# STeaMi-FP5-Microphone.net
KiCad netlist of a schematic drawn in Altium Designer
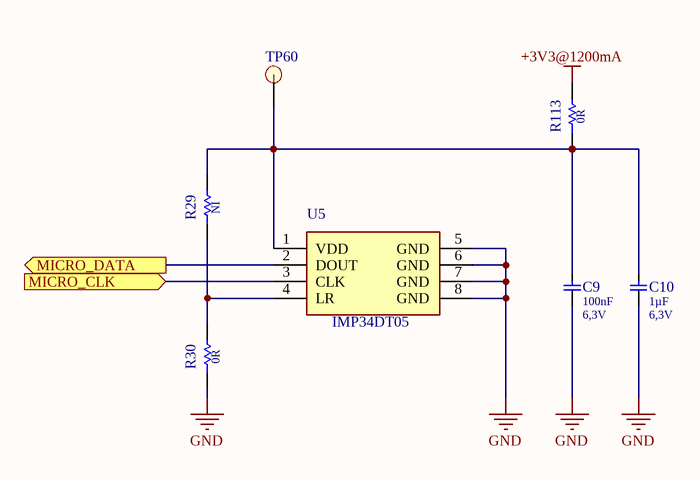
[diagram p0: STeaMi-FP5-Microphone.SchDoc]

(export (version "E")
  (design (tool "Eeschema 10.0.6"))
  (components
    (comp (ref "C9")
      (value "~")
      (footprint "0402-CAP")
      (description "CAP CER 100nF 6,3V X5R 0402")
      (fields
        (field (name "MANUFACTURER") "Kyocera AVX")
        (field (name "MANUFACTURER PART NUMBER") "0402YD104KAT2A")
        (field (name "CAPACITANCE") "100nF")
        (field (name "VOLTAGE") "6,3V")
        (field (name "CREATED BY") "EAG")
        (field (name "CHECKED BY") "*")
      )
      (libsource (lib "ComponentDB") (part "CAP_SYMBOL"))
    )
    (comp (ref "C10")
      (value "~")
      (footprint "0402-CAP")
      (description "CAP CER 1µF 6,3V X5R 0402")
      (fields
        (field (name "MANUFACTURER") "Taiyo Yuden")
        (field (name "MANUFACTURER PART NUMBER") "JMK105BJ105KV-F")
        (field (name "CAPACITANCE") "1µF")
        (field (name "VOLTAGE") "6,3V")
        (field (name "CREATED BY") "EAG")
        (field (name "CHECKED BY") "*")
      )
      (libsource (lib "ComponentDB") (part "CAP_SYMBOL"))
    )
    (comp (ref "R29")
      (value "~")
      (footprint "RESC1005X40N_0402")
      (description "NI")
      (fields
        (field (name "POWER") "0,1")
        (field (name "RESISTANCE") "NI")
        (field (name "PART NUMBER") "NI-1%-0,1W-0603")
        (field (name "CREATED BY") "MSA")
      )
      (libsource (lib "ComponentDB") (part "RES_SYMBOL"))
    )
    (comp (ref "R30")
      (value "~")
      (footprint "RESC1005X40N_0402")
      (description "RES CMS 0R5%-0,0625W-0402")
      (fields
        (field (name "MANUFACTURER") "Yageo")
        (field (name "MANUFACTURER PART NUMBER") "RC0402JR-100RL")
        (field (name "RESISTANCE") "0R")
        (field (name "CREATED BY") "EAG")
      )
      (libsource (lib "ComponentDB") (part "RES_SYMBOL"))
    )
    (comp (ref "R113")
      (value "~")
      (footprint "RESC1005X40N_0402")
      (description "RES CMS 0R5%-0,0625W-0402")
      (fields
        (field (name "MANUFACTURER") "Yageo")
        (field (name "MANUFACTURER PART NUMBER") "RC0402JR-100RL")
        (field (name "RESISTANCE") "0R")
        (field (name "CREATED BY") "EAG")
      )
      (libsource (lib "ComponentDB") (part "RES_SYMBOL"))
    )
    (comp (ref "TP60")
      (value "PAD")
      (footprint "Testpoint 1mm")
      (description "TESTPOINTPAD")
      (fields
        (field (name "MANUFACTURER") "Smartembed")
        (field (name "MANUFACTURER PART NUMBER") "TESTPOINT")
        (field (name "CREATED BY") "EAG")
      )
      (libsource (lib "ComponentDB") (part "TESTPOINT"))
    )
    (comp (ref "U5")
      (value "~")
      (footprint "IMP34DT05")
      (description "MEMS audio sensor omnidirectional digital microphone dor industrial application")
      (fields
        (field (name "MANUFACTURER") "STMicroelectronics")
        (field (name "MANUFACTURER PART NUMBER") "IMP34DT05")
        (field (name "PART NUMBER") "IMP34DT05")
        (field (name "CREATED BY") "EAG")
        (field (name "CHECKED BY") "*")
      )
      (libsource (lib "ComponentDB") (part "IMP34DT05"))
    )
  )
  (nets
    (net (code "1") (name "+3V3@1200mA") (class "Default")
      (node (ref "R113") (pin "2") (pinfunction "2_2") (pintype "passive"))
    )
    (net (code "2") (name "/MICRO_CLK") (class "Default")
      (node (ref "U5") (pin "3") (pinfunction "CLK_3") (pintype "passive"))
    )
    (net (code "3") (name "/MICRO_DATA") (class "Default")
      (node (ref "U5") (pin "2") (pinfunction "DOUT_2") (pintype "passive"))
    )
    (net (code "4") (name "GND") (class "Default")
      (node (ref "C10") (pin "1") (pinfunction "1_1") (pintype "passive"))
      (node (ref "C9") (pin "1") (pinfunction "1_1") (pintype "passive"))
      (node (ref "R30") (pin "1") (pinfunction "1_1") (pintype "passive"))
      (node (ref "U5") (pin "5") (pinfunction "GND_5") (pintype "passive"))
      (node (ref "U5") (pin "6") (pinfunction "GND_6") (pintype "passive"))
      (node (ref "U5") (pin "7") (pinfunction "GND_7") (pintype "passive"))
      (node (ref "U5") (pin "8") (pinfunction "GND_8") (pintype "passive"))
    )
    (net (code "5") (name "Net-(U5-LR)") (class "Default")
      (node (ref "R29") (pin "1") (pinfunction "1_1") (pintype "passive"))
      (node (ref "R30") (pin "2") (pinfunction "2_2") (pintype "passive"))
      (node (ref "U5") (pin "4") (pinfunction "LR_4") (pintype "passive"))
    )
    (net (code "6") (name "Net-(U5-VDD)") (class "Default")
      (node (ref "C10") (pin "2") (pinfunction "2_2") (pintype "passive"))
      (node (ref "C9") (pin "2") (pinfunction "2_2") (pintype "passive"))
      (node (ref "R113") (pin "1") (pinfunction "1_1") (pintype "passive"))
      (node (ref "R29") (pin "2") (pinfunction "2_2") (pintype "passive"))
      (node (ref "TP60") (pin "1") (pinfunction "1_1") (pintype "passive"))
      (node (ref "U5") (pin "1") (pinfunction "VDD_1") (pintype "passive"))
    )
  )
)
